# Watch-It-BOTTOM.net
KiCad netlist of a schematic drawn in EAGLE
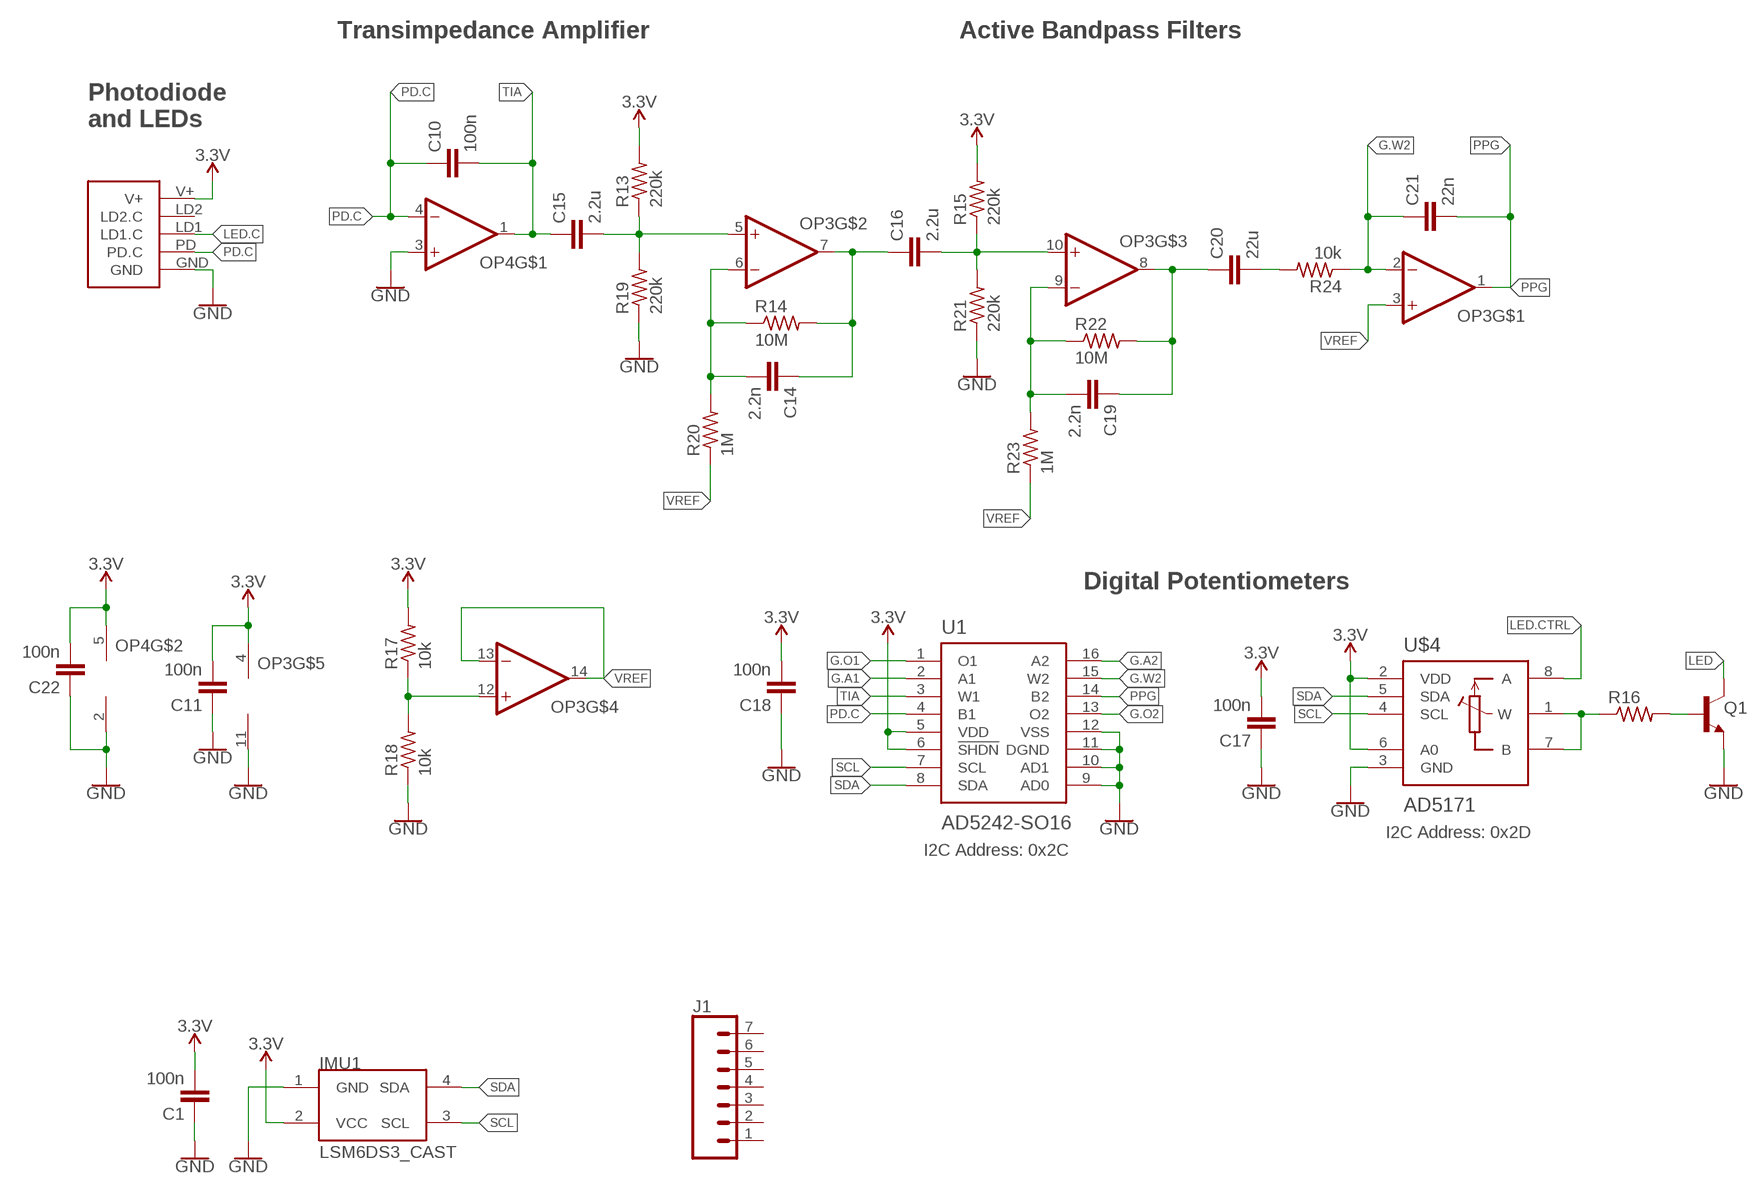
[diagram p0: schematic, sheet 1]

(export (version "E")
  (design (tool "Eeschema 10.0.6"))
  (components
    (comp (ref "C1")
      (value "100n")
      (footprint "eagle-import:C0603")
      (libsource (lib "eagle-import") (part "CAPACITOR0603"))
    )
    (comp (ref "C10")
      (value "100n")
      (footprint "eagle-import:C0603")
      (libsource (lib "eagle-import") (part "CAPACITOR0603"))
    )
    (comp (ref "C11")
      (value "100n")
      (footprint "eagle-import:C0603")
      (libsource (lib "eagle-import") (part "CAPACITOR0603"))
    )
    (comp (ref "C14")
      (value "2.2n")
      (footprint "eagle-import:C0603")
      (libsource (lib "eagle-import") (part "CAPACITOR0603"))
    )
    (comp (ref "C15")
      (value "2.2u")
      (footprint "eagle-import:C0603")
      (libsource (lib "eagle-import") (part "CAPACITOR0603"))
    )
    (comp (ref "C16")
      (value "2.2u")
      (footprint "eagle-import:C0603")
      (libsource (lib "eagle-import") (part "CAPACITOR0603"))
    )
    (comp (ref "C17")
      (value "100n")
      (footprint "eagle-import:C0603")
      (libsource (lib "eagle-import") (part "CAPACITOR0603"))
    )
    (comp (ref "C18")
      (value "100n")
      (footprint "eagle-import:C0603")
      (libsource (lib "eagle-import") (part "CAPACITOR0603"))
    )
    (comp (ref "C19")
      (value "2.2n")
      (footprint "eagle-import:C0603")
      (libsource (lib "eagle-import") (part "CAPACITOR0603"))
    )
    (comp (ref "C20")
      (value "22u")
      (footprint "eagle-import:C0603")
      (libsource (lib "eagle-import") (part "CAPACITOR0603"))
    )
    (comp (ref "C21")
      (value "22n")
      (footprint "eagle-import:C0603")
      (libsource (lib "eagle-import") (part "CAPACITOR0603"))
    )
    (comp (ref "C22")
      (value "100n")
      (footprint "eagle-import:C0603")
      (libsource (lib "eagle-import") (part "CAPACITOR0603"))
    )
    (comp (ref "IMU1")
      (value "LSM6DS3_CAST")
      (footprint "eagle-import:LSM6DS3_CAST")
      (libsource (lib "eagle-import") (part "LSM6DS3_CAST"))
    )
    (comp (ref "J1")
      (value "CONN_07")
      (footprint "eagle-import:1X07")
      (libsource (lib "eagle-import") (part "CONN_07"))
    )
    (comp (ref "OP3")
      (value "OP-QUAD-SO14")
      (footprint "eagle-import:SO14")
      (libsource (lib "eagle-import") (part "OP-QUAD-SO14"))
    )
    (comp (ref "OP4")
      (value "OP-SINGLEOT")
      (footprint "eagle-import:SOT23-5")
      (libsource (lib "eagle-import") (part "OP-SINGLEOT"))
    )
    (comp (ref "Q1")
      (value "NPN-GENERIC")
      (footprint "eagle-import:SOT23-3")
      (libsource (lib "eagle-import") (part "NPN-GENERIC"))
    )
    (comp (ref "R13")
      (value "220k")
      (footprint "eagle-import:R0603")
      (libsource (lib "eagle-import") (part "RESISTOR0603"))
    )
    (comp (ref "R14")
      (value "10M")
      (footprint "eagle-import:R0603")
      (libsource (lib "eagle-import") (part "RESISTOR0603"))
    )
    (comp (ref "R15")
      (value "220k")
      (footprint "eagle-import:R0603")
      (libsource (lib "eagle-import") (part "RESISTOR0603"))
    )
    (comp (ref "R16")
      (value "RESISTOR0603")
      (footprint "eagle-import:R0603")
      (libsource (lib "eagle-import") (part "RESISTOR0603"))
    )
    (comp (ref "R17")
      (value "10k")
      (footprint "eagle-import:R0402")
      (libsource (lib "eagle-import") (part "RESISTOR0402"))
    )
    (comp (ref "R18")
      (value "10k")
      (footprint "eagle-import:R0402")
      (libsource (lib "eagle-import") (part "RESISTOR0402"))
    )
    (comp (ref "R19")
      (value "220k")
      (footprint "eagle-import:R0603")
      (libsource (lib "eagle-import") (part "RESISTOR0603"))
    )
    (comp (ref "R20")
      (value "1M")
      (footprint "eagle-import:R0603")
      (libsource (lib "eagle-import") (part "RESISTOR0603"))
    )
    (comp (ref "R21")
      (value "220k")
      (footprint "eagle-import:R0603")
      (libsource (lib "eagle-import") (part "RESISTOR0603"))
    )
    (comp (ref "R22")
      (value "10M")
      (footprint "eagle-import:R0603")
      (libsource (lib "eagle-import") (part "RESISTOR0603"))
    )
    (comp (ref "R23")
      (value "1M")
      (footprint "eagle-import:R0603")
      (libsource (lib "eagle-import") (part "RESISTOR0603"))
    )
    (comp (ref "R24")
      (value "10k")
      (footprint "eagle-import:R0603")
      (libsource (lib "eagle-import") (part "RESISTOR0603"))
    )
    (comp (ref "U$3")
      (value "PPG.MODULE.2")
      (footprint "eagle-import:PPG.MODULE.2")
      (libsource (lib "eagle-import") (part "PPG.MODULE.2"))
    )
    (comp (ref "U$4")
      (value "AD5171")
      (footprint "eagle-import:SOT-23-8")
      (libsource (lib "eagle-import") (part "AD5171"))
    )
    (comp (ref "U1")
      (value "AD5242-SO16")
      (footprint "eagle-import:SO16")
      (libsource (lib "eagle-import") (part "AD5242-SO16"))
    )
  )
  (nets
    (net (code "1") (name "3.3V") (class "Default")
      (node (ref "C1") (pin "2") (pinfunction "2_2") (pintype "passive"))
      (node (ref "C11") (pin "2") (pinfunction "2_2") (pintype "passive"))
      (node (ref "C17") (pin "2") (pinfunction "2_2") (pintype "passive"))
      (node (ref "C18") (pin "2") (pinfunction "2_2") (pintype "passive"))
      (node (ref "C22") (pin "2") (pinfunction "2_2") (pintype "passive"))
      (node (ref "IMU1") (pin "2") (pinfunction "VCC_2") (pintype "bidirectional"))
      (node (ref "OP3") (pin "4") (pinfunction "V+_4") (pintype "power_in"))
      (node (ref "OP4") (pin "5") (pinfunction "V+_5") (pintype "power_in"))
      (node (ref "R13") (pin "2") (pinfunction "2_2") (pintype "passive"))
      (node (ref "R15") (pin "2") (pinfunction "2_2") (pintype "passive"))
      (node (ref "R17") (pin "2") (pinfunction "2_2") (pintype "passive"))
      (node (ref "U$3") (pin "V+") (pinfunction "V+_V+") (pintype "bidirectional"))
      (node (ref "U$4") (pin "2") (pinfunction "VDD_2") (pintype "bidirectional"))
      (node (ref "U$4") (pin "6") (pinfunction "A0_6") (pintype "bidirectional"))
      (node (ref "U1") (pin "5") (pinfunction "VDD_5") (pintype "bidirectional"))
      (node (ref "U1") (pin "6") (pinfunction "~{SHDN}_6") (pintype "bidirectional"))
    )
    (net (code "2") (name "G.A1") (class "Default")
      (node (ref "U1") (pin "2") (pinfunction "A1_2") (pintype "bidirectional"))
    )
    (net (code "3") (name "G.A2") (class "Default")
      (node (ref "U1") (pin "16") (pinfunction "A2_16") (pintype "bidirectional"))
    )
    (net (code "4") (name "G.O1") (class "Default")
      (node (ref "U1") (pin "1") (pinfunction "O1_1") (pintype "bidirectional"))
    )
    (net (code "5") (name "G.O2") (class "Default")
      (node (ref "U1") (pin "13") (pinfunction "O2_13") (pintype "bidirectional"))
    )
    (net (code "6") (name "G.W2") (class "Default")
      (node (ref "C21") (pin "1") (pinfunction "1_1") (pintype "passive"))
      (node (ref "OP3") (pin "2") (pinfunction "-IN_2") (pintype "input"))
      (node (ref "R24") (pin "1") (pinfunction "1_1") (pintype "passive"))
      (node (ref "U1") (pin "15") (pinfunction "W2_15") (pintype "bidirectional"))
    )
    (net (code "7") (name "GND") (class "Default")
      (node (ref "C1") (pin "1") (pinfunction "1_1") (pintype "passive"))
      (node (ref "C11") (pin "1") (pinfunction "1_1") (pintype "passive"))
      (node (ref "C17") (pin "1") (pinfunction "1_1") (pintype "passive"))
      (node (ref "C18") (pin "1") (pinfunction "1_1") (pintype "passive"))
      (node (ref "C22") (pin "1") (pinfunction "1_1") (pintype "passive"))
      (node (ref "IMU1") (pin "1") (pinfunction "GND_1") (pintype "bidirectional"))
      (node (ref "OP3") (pin "11") (pinfunction "V-_11") (pintype "power_in"))
      (node (ref "OP4") (pin "2") (pinfunction "V-_2") (pintype "power_in"))
      (node (ref "OP4") (pin "3") (pinfunction "+IN_3") (pintype "input"))
      (node (ref "Q1") (pin "2") (pinfunction "E_2") (pintype "passive"))
      (node (ref "R18") (pin "1") (pinfunction "1_1") (pintype "passive"))
      (node (ref "R19") (pin "1") (pinfunction "1_1") (pintype "passive"))
      (node (ref "R21") (pin "1") (pinfunction "1_1") (pintype "passive"))
      (node (ref "U$3") (pin "GND") (pinfunction "GND_GND") (pintype "bidirectional"))
      (node (ref "U$4") (pin "3") (pinfunction "GND_3") (pintype "bidirectional"))
      (node (ref "U1") (pin "10") (pinfunction "AD1_10") (pintype "bidirectional"))
      (node (ref "U1") (pin "11") (pinfunction "DGND_11") (pintype "bidirectional"))
      (node (ref "U1") (pin "12") (pinfunction "VSS_12") (pintype "bidirectional"))
      (node (ref "U1") (pin "9") (pinfunction "AD0_9") (pintype "bidirectional"))
    )
    (net (code "8") (name "LED") (class "Default")
      (node (ref "Q1") (pin "3") (pinfunction "C_3") (pintype "passive"))
    )
    (net (code "9") (name "LED.C") (class "Default")
      (node (ref "U$3") (pin "LD1") (pinfunction "LD1.C_LD1") (pintype "bidirectional"))
    )
    (net (code "10") (name "LED.CTRL") (class "Default")
      (node (ref "U$4") (pin "8") (pinfunction "A_8") (pintype "bidirectional"))
    )
    (net (code "11") (name "Net-(C20-Pad2)") (class "Default")
      (node (ref "C20") (pin "2") (pinfunction "2_2") (pintype "passive"))
      (node (ref "R24") (pin "2") (pinfunction "2_2") (pintype "passive"))
    )
    (net (code "12") (name "Net-(OP3B-+IN)") (class "Default")
      (node (ref "C15") (pin "2") (pinfunction "2_2") (pintype "passive"))
      (node (ref "OP3") (pin "5") (pinfunction "+IN_5") (pintype "input"))
      (node (ref "R13") (pin "1") (pinfunction "1_1") (pintype "passive"))
      (node (ref "R19") (pin "2") (pinfunction "2_2") (pintype "passive"))
    )
    (net (code "13") (name "Net-(OP3B--IN)") (class "Default")
      (node (ref "C14") (pin "2") (pinfunction "2_2") (pintype "passive"))
      (node (ref "OP3") (pin "6") (pinfunction "-IN_6") (pintype "input"))
      (node (ref "R14") (pin "1") (pinfunction "1_1") (pintype "passive"))
      (node (ref "R20") (pin "2") (pinfunction "2_2") (pintype "passive"))
    )
    (net (code "14") (name "Net-(OP3B-OUT)") (class "Default")
      (node (ref "C14") (pin "1") (pinfunction "1_1") (pintype "passive"))
      (node (ref "C16") (pin "1") (pinfunction "1_1") (pintype "passive"))
      (node (ref "OP3") (pin "7") (pinfunction "OUT_7") (pintype "output"))
      (node (ref "R14") (pin "2") (pinfunction "2_2") (pintype "passive"))
    )
    (net (code "15") (name "Net-(OP3C-+IN)") (class "Default")
      (node (ref "C16") (pin "2") (pinfunction "2_2") (pintype "passive"))
      (node (ref "OP3") (pin "10") (pinfunction "+IN_10") (pintype "input"))
      (node (ref "R15") (pin "1") (pinfunction "1_1") (pintype "passive"))
      (node (ref "R21") (pin "2") (pinfunction "2_2") (pintype "passive"))
    )
    (net (code "16") (name "Net-(OP3C--IN)") (class "Default")
      (node (ref "C19") (pin "2") (pinfunction "2_2") (pintype "passive"))
      (node (ref "OP3") (pin "9") (pinfunction "-IN_9") (pintype "input"))
      (node (ref "R22") (pin "1") (pinfunction "1_1") (pintype "passive"))
      (node (ref "R23") (pin "2") (pinfunction "2_2") (pintype "passive"))
    )
    (net (code "17") (name "Net-(OP3C-OUT)") (class "Default")
      (node (ref "C19") (pin "1") (pinfunction "1_1") (pintype "passive"))
      (node (ref "C20") (pin "1") (pinfunction "1_1") (pintype "passive"))
      (node (ref "OP3") (pin "8") (pinfunction "OUT_8") (pintype "output"))
      (node (ref "R22") (pin "2") (pinfunction "2_2") (pintype "passive"))
    )
    (net (code "18") (name "Net-(OP3D-+IN)") (class "Default")
      (node (ref "OP3") (pin "12") (pinfunction "+IN_12") (pintype "input"))
      (node (ref "R17") (pin "1") (pinfunction "1_1") (pintype "passive"))
      (node (ref "R18") (pin "2") (pinfunction "2_2") (pintype "passive"))
    )
    (net (code "19") (name "Net-(Q1-B)") (class "Default")
      (node (ref "Q1") (pin "1") (pinfunction "B_1") (pintype "passive"))
      (node (ref "R16") (pin "2") (pinfunction "2_2") (pintype "passive"))
    )
    (net (code "20") (name "Net-(U$4-B)") (class "Default")
      (node (ref "R16") (pin "1") (pinfunction "1_1") (pintype "passive"))
      (node (ref "U$4") (pin "1") (pinfunction "W_1") (pintype "bidirectional"))
      (node (ref "U$4") (pin "7") (pinfunction "B_7") (pintype "bidirectional"))
    )
    (net (code "21") (name "PD.C") (class "Default")
      (node (ref "C10") (pin "1") (pinfunction "1_1") (pintype "passive"))
      (node (ref "OP4") (pin "4") (pinfunction "-IN_4") (pintype "input"))
      (node (ref "U$3") (pin "PD") (pinfunction "PD.C_PD") (pintype "bidirectional"))
      (node (ref "U1") (pin "4") (pinfunction "B1_4") (pintype "bidirectional"))
    )
    (net (code "22") (name "PPG") (class "Default")
      (node (ref "C21") (pin "2") (pinfunction "2_2") (pintype "passive"))
      (node (ref "OP3") (pin "1") (pinfunction "OUT_1") (pintype "output"))
      (node (ref "U1") (pin "14") (pinfunction "B2_14") (pintype "bidirectional"))
    )
    (net (code "23") (name "SCL") (class "Default")
      (node (ref "IMU1") (pin "3") (pinfunction "SCL_3") (pintype "bidirectional"))
      (node (ref "U$4") (pin "4") (pinfunction "SCL_4") (pintype "bidirectional"))
      (node (ref "U1") (pin "7") (pinfunction "SCL_7") (pintype "bidirectional"))
    )
    (net (code "24") (name "SDA") (class "Default")
      (node (ref "IMU1") (pin "4") (pinfunction "SDA_4") (pintype "bidirectional"))
      (node (ref "U$4") (pin "5") (pinfunction "SDA_5") (pintype "bidirectional"))
      (node (ref "U1") (pin "8") (pinfunction "SDA_8") (pintype "bidirectional"))
    )
    (net (code "25") (name "TIA") (class "Default")
      (node (ref "C10") (pin "2") (pinfunction "2_2") (pintype "passive"))
      (node (ref "C15") (pin "1") (pinfunction "1_1") (pintype "passive"))
      (node (ref "OP4") (pin "1") (pinfunction "OUT_1") (pintype "output"))
      (node (ref "U1") (pin "3") (pinfunction "W1_3") (pintype "bidirectional"))
    )
    (net (code "26") (name "VREF") (class "Default")
      (node (ref "OP3") (pin "13") (pinfunction "-IN_13") (pintype "input"))
      (node (ref "OP3") (pin "14") (pinfunction "OUT_14") (pintype "output"))
      (node (ref "OP3") (pin "3") (pinfunction "+IN_3") (pintype "input"))
      (node (ref "R20") (pin "1") (pinfunction "1_1") (pintype "passive"))
      (node (ref "R23") (pin "1") (pinfunction "1_1") (pintype "passive"))
    )
    (net (code "27") (name "unconnected-(J1-Pad1)") (class "Default")
      (node (ref "J1") (pin "1") (pinfunction "1_1") (pintype "passive"))
    )
    (net (code "28") (name "unconnected-(J1-Pad2)") (class "Default")
      (node (ref "J1") (pin "2") (pinfunction "2_2") (pintype "passive"))
    )
    (net (code "29") (name "unconnected-(J1-Pad3)") (class "Default")
      (node (ref "J1") (pin "3") (pinfunction "3_3") (pintype "passive"))
    )
    (net (code "30") (name "unconnected-(J1-Pad4)") (class "Default")
      (node (ref "J1") (pin "4") (pinfunction "4_4") (pintype "passive"))
    )
    (net (code "31") (name "unconnected-(J1-Pad5)") (class "Default")
      (node (ref "J1") (pin "5") (pinfunction "5_5") (pintype "passive"))
    )
    (net (code "32") (name "unconnected-(J1-Pad6)") (class "Default")
      (node (ref "J1") (pin "6") (pinfunction "6_6") (pintype "passive"))
    )
    (net (code "33") (name "unconnected-(J1-Pad7)") (class "Default")
      (node (ref "J1") (pin "7") (pinfunction "7_7") (pintype "passive"))
    )
    (net (code "34") (name "unconnected-(U$3-LD2.C-PadLD2)") (class "Default")
      (node (ref "U$3") (pin "LD2") (pinfunction "LD2.C_LD2") (pintype "bidirectional"))
    )
  )
)
